# CzujnikWilgotnosciGleby_Rafal_Brauner.net
KiCad netlist of a schematic drawn in EAGLE
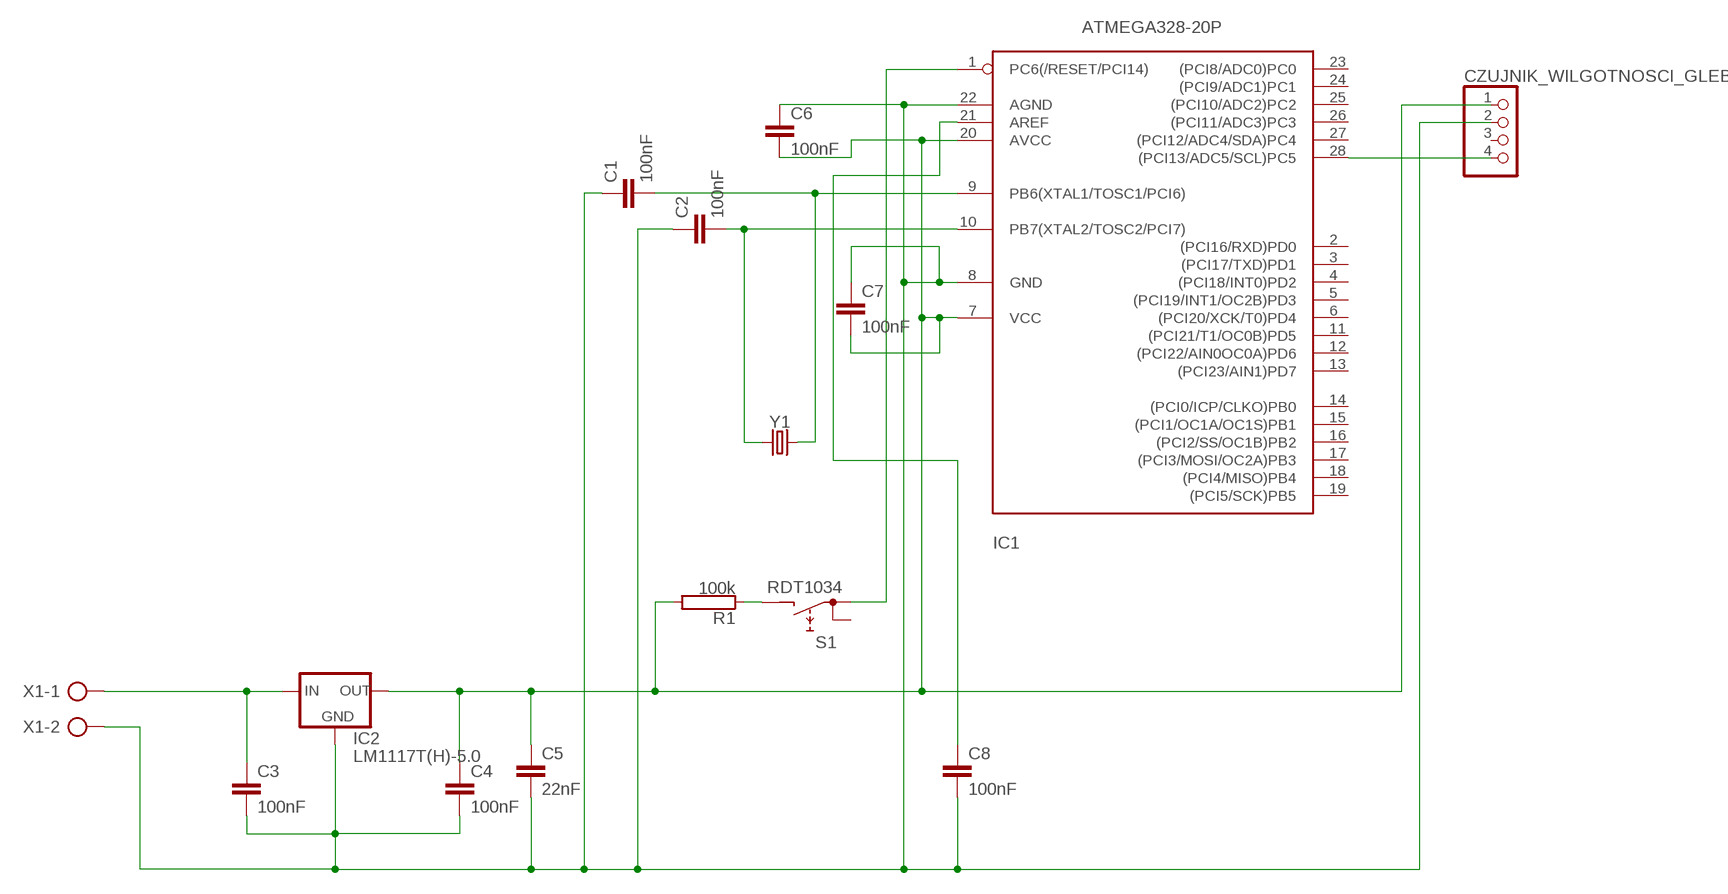
[diagram p0: schematic, sheet 1]

(export (version "E")
  (design (tool "Eeschema 10.0.6"))
  (components
    (comp (ref "C1")
      (value "100nF")
      (footprint "eagle-import:C2.5-3")
      (libsource (lib "eagle-import") (part "C2,5-3"))
    )
    (comp (ref "C2")
      (value "100nF")
      (footprint "eagle-import:C2.5-3")
      (libsource (lib "eagle-import") (part "C2,5-3"))
    )
    (comp (ref "C3")
      (value "100nF")
      (footprint "eagle-import:C2.5-3")
      (libsource (lib "eagle-import") (part "C2,5-3"))
    )
    (comp (ref "C4")
      (value "100nF")
      (footprint "eagle-import:C2.5-3")
      (libsource (lib "eagle-import") (part "C2,5-3"))
    )
    (comp (ref "C5")
      (value "22nF")
      (footprint "eagle-import:C2.5-3")
      (libsource (lib "eagle-import") (part "C2,5-3"))
    )
    (comp (ref "C6")
      (value "100nF")
      (footprint "eagle-import:C2.5-3")
      (libsource (lib "eagle-import") (part "C2,5-3"))
    )
    (comp (ref "C7")
      (value "100nF")
      (footprint "eagle-import:C2.5-3")
      (libsource (lib "eagle-import") (part "C2,5-3"))
    )
    (comp (ref "C8")
      (value "100nF")
      (footprint "eagle-import:C2.5-3")
      (libsource (lib "eagle-import") (part "C2,5-3"))
    )
    (comp (ref "CZUJNIK_WILGOTNOSCI_GLEBY")
      (value "PINHD-1X4")
      (footprint "eagle-import:1X04")
      (libsource (lib "eagle-import") (part "PINHD-1X4"))
    )
    (comp (ref "IC1")
      (value "ATMEGA328-20P")
      (footprint "eagle-import:DIL28-3")
      (libsource (lib "eagle-import") (part "ATMEGA328P-20"))
    )
    (comp (ref "IC2")
      (value "LM1117T(H)-5.0")
      (footprint "eagle-import:TO220H")
      (fields (field (name "MF") "Texas Instruments") (field (name "MPN") "LM1117T-5.0"))
      (libsource (lib "eagle-import") (part "LM1117?-T(H)5.0"))
    )
    (comp (ref "R1")
      (value "100k")
      (footprint "eagle-import:AC01")
      (libsource (lib "eagle-import") (part "RAC01"))
    )
    (comp (ref "S1")
      (value "RDT1034")
      (footprint "eagle-import:RDT1034")
      (libsource (lib "eagle-import") (part "RDT1034"))
    )
    (comp (ref "X1")
      (value "AK300/2")
      (footprint "eagle-import:AK300_2")
      (libsource (lib "eagle-import") (part "AK300/2"))
    )
    (comp (ref "Y1")
      (value "CRYSTALPTH-HC49US")
      (footprint "eagle-import:HC49US")
      (libsource (lib "eagle-import") (part "CRYSTALPTH-HC49US"))
    )
  )
  (nets
    (net (code "1") (name "Net-(IC1-(PCI13{slash}ADC5{slash}SCL)PC5)") (class "Default")
      (node (ref "CZUJNIK_WILGOTNOSCI_GLEBY") (pin "4") (pinfunction "4_4") (pintype "passive"))
      (node (ref "IC1") (pin "28") (pinfunction "(PCI13/ADC5/SCL)PC5_28") (pintype "bidirectional"))
    )
    (net (code "2") (name "Net-(IC1-AGND)") (class "Default")
      (node (ref "C1") (pin "1") (pinfunction "1_1") (pintype "passive"))
      (node (ref "C2") (pin "1") (pinfunction "1_1") (pintype "passive"))
      (node (ref "C3") (pin "2") (pinfunction "2_2") (pintype "passive"))
      (node (ref "C4") (pin "2") (pinfunction "2_2") (pintype "passive"))
      (node (ref "C5") (pin "2") (pinfunction "2_2") (pintype "passive"))
      (node (ref "C6") (pin "1") (pinfunction "1_1") (pintype "passive"))
      (node (ref "C7") (pin "1") (pinfunction "1_1") (pintype "passive"))
      (node (ref "C8") (pin "2") (pinfunction "2_2") (pintype "passive"))
      (node (ref "CZUJNIK_WILGOTNOSCI_GLEBY") (pin "2") (pinfunction "2_2") (pintype "passive"))
      (node (ref "IC1") (pin "22") (pinfunction "AGND_22") (pintype "bidirectional"))
      (node (ref "IC1") (pin "8") (pinfunction "GND_8") (pintype "bidirectional"))
      (node (ref "IC2") (pin "1") (pinfunction "GND_1") (pintype "input"))
      (node (ref "X1") (pin "2") (pinfunction "KL_2") (pintype "passive"))
    )
    (net (code "3") (name "Net-(IC1-AREF)") (class "Default")
      (node (ref "C8") (pin "1") (pinfunction "1_1") (pintype "passive"))
      (node (ref "IC1") (pin "21") (pinfunction "AREF_21") (pintype "bidirectional"))
    )
    (net (code "4") (name "Net-(IC1-AVCC)") (class "Default")
      (node (ref "C4") (pin "1") (pinfunction "1_1") (pintype "passive"))
      (node (ref "C5") (pin "1") (pinfunction "1_1") (pintype "passive"))
      (node (ref "C6") (pin "2") (pinfunction "2_2") (pintype "passive"))
      (node (ref "C7") (pin "2") (pinfunction "2_2") (pintype "passive"))
      (node (ref "CZUJNIK_WILGOTNOSCI_GLEBY") (pin "1") (pinfunction "1_1") (pintype "passive"))
      (node (ref "IC1") (pin "20") (pinfunction "AVCC_20") (pintype "bidirectional"))
      (node (ref "IC1") (pin "7") (pinfunction "VCC_7") (pintype "bidirectional"))
      (node (ref "IC2") (pin "2") (pinfunction "OUT_2") (pintype "passive"))
      (node (ref "R1") (pin "2") (pinfunction "2_2") (pintype "passive"))
    )
    (net (code "5") (name "Net-(IC1-PB6(XTAL1{slash}TOSC1{slash}PCI6))") (class "Default")
      (node (ref "C1") (pin "2") (pinfunction "2_2") (pintype "passive"))
      (node (ref "IC1") (pin "9") (pinfunction "PB6(XTAL1/TOSC1/PCI6)_9") (pintype "bidirectional"))
      (node (ref "Y1") (pin "2") (pinfunction "2_2") (pintype "passive"))
    )
    (net (code "6") (name "Net-(IC1-PB7(XTAL2{slash}TOSC2{slash}PCI7))") (class "Default")
      (node (ref "C2") (pin "2") (pinfunction "2_2") (pintype "passive"))
      (node (ref "IC1") (pin "10") (pinfunction "PB7(XTAL2/TOSC2/PCI7)_10") (pintype "bidirectional"))
      (node (ref "Y1") (pin "1") (pinfunction "1_1") (pintype "passive"))
    )
    (net (code "7") (name "Net-(IC1-PC6({slash}RESET{slash}PCI14))") (class "Default")
      (node (ref "IC1") (pin "1") (pinfunction "PC6(/RESET/PCI14)_1") (pintype "bidirectional"))
      (node (ref "S1") (pin "A1") (pinfunction "A1_A1") (pintype "passive"))
    )
    (net (code "8") (name "Net-(IC2-IN)") (class "Default")
      (node (ref "C3") (pin "1") (pinfunction "1_1") (pintype "passive"))
      (node (ref "IC2") (pin "3") (pinfunction "IN_3") (pintype "input"))
      (node (ref "X1") (pin "1") (pinfunction "KL_1") (pintype "passive"))
    )
    (net (code "9") (name "Net-(R1-Pad1)") (class "Default")
      (node (ref "R1") (pin "1") (pinfunction "1_1") (pintype "passive"))
      (node (ref "S1") (pin "B") (pinfunction "B_B") (pintype "passive"))
    )
    (net (code "10") (name "unconnected-(CZUJNIK_WILGOTNOSCI_GLEBY-Pad3)") (class "Default")
      (node (ref "CZUJNIK_WILGOTNOSCI_GLEBY") (pin "3") (pinfunction "3_3") (pintype "passive"))
    )
    (net (code "11") (name "unconnected-(IC1-(PCI0{slash}ICP{slash}CLKO)PB0-Pad14)") (class "Default")
      (node (ref "IC1") (pin "14") (pinfunction "(PCI0/ICP/CLKO)PB0_14") (pintype "bidirectional"))
    )
    (net (code "12") (name "unconnected-(IC1-(PCI1{slash}OC1A{slash}OC1S)PB1-Pad15)") (class "Default")
      (node (ref "IC1") (pin "15") (pinfunction "(PCI1/OC1A/OC1S)PB1_15") (pintype "bidirectional"))
    )
    (net (code "13") (name "unconnected-(IC1-(PCI2{slash}SS{slash}OC1B)PB2-Pad16)") (class "Default")
      (node (ref "IC1") (pin "16") (pinfunction "(PCI2/SS/OC1B)PB2_16") (pintype "bidirectional"))
    )
    (net (code "14") (name "unconnected-(IC1-(PCI3{slash}MOSI{slash}OC2A)PB3-Pad17)") (class "Default")
      (node (ref "IC1") (pin "17") (pinfunction "(PCI3/MOSI/OC2A)PB3_17") (pintype "bidirectional"))
    )
    (net (code "15") (name "unconnected-(IC1-(PCI4{slash}MISO)PB4-Pad18)") (class "Default")
      (node (ref "IC1") (pin "18") (pinfunction "(PCI4/MISO)PB4_18") (pintype "bidirectional"))
    )
    (net (code "16") (name "unconnected-(IC1-(PCI5{slash}SCK)PB5-Pad19)") (class "Default")
      (node (ref "IC1") (pin "19") (pinfunction "(PCI5/SCK)PB5_19") (pintype "bidirectional"))
    )
    (net (code "17") (name "unconnected-(IC1-(PCI8{slash}ADC0)PC0-Pad23)") (class "Default")
      (node (ref "IC1") (pin "23") (pinfunction "(PCI8/ADC0)PC0_23") (pintype "bidirectional"))
    )
    (net (code "18") (name "unconnected-(IC1-(PCI9{slash}ADC1)PC1-Pad24)") (class "Default")
      (node (ref "IC1") (pin "24") (pinfunction "(PCI9/ADC1)PC1_24") (pintype "bidirectional"))
    )
    (net (code "19") (name "unconnected-(IC1-(PCI10{slash}ADC2)PC2-Pad25)") (class "Default")
      (node (ref "IC1") (pin "25") (pinfunction "(PCI10/ADC2)PC2_25") (pintype "bidirectional"))
    )
    (net (code "20") (name "unconnected-(IC1-(PCI11{slash}ADC3)PC3-Pad26)") (class "Default")
      (node (ref "IC1") (pin "26") (pinfunction "(PCI11/ADC3)PC3_26") (pintype "bidirectional"))
    )
    (net (code "21") (name "unconnected-(IC1-(PCI12{slash}ADC4{slash}SDA)PC4-Pad27)") (class "Default")
      (node (ref "IC1") (pin "27") (pinfunction "(PCI12/ADC4/SDA)PC4_27") (pintype "bidirectional"))
    )
    (net (code "22") (name "unconnected-(IC1-(PCI16{slash}RXD)PD0-Pad2)") (class "Default")
      (node (ref "IC1") (pin "2") (pinfunction "(PCI16/RXD)PD0_2") (pintype "bidirectional"))
    )
    (net (code "23") (name "unconnected-(IC1-(PCI17{slash}TXD)PD1-Pad3)") (class "Default")
      (node (ref "IC1") (pin "3") (pinfunction "(PCI17/TXD)PD1_3") (pintype "bidirectional"))
    )
    (net (code "24") (name "unconnected-(IC1-(PCI18{slash}INT0)PD2-Pad4)") (class "Default")
      (node (ref "IC1") (pin "4") (pinfunction "(PCI18/INT0)PD2_4") (pintype "bidirectional"))
    )
    (net (code "25") (name "unconnected-(IC1-(PCI19{slash}INT1{slash}OC2B)PD3-Pad5)") (class "Default")
      (node (ref "IC1") (pin "5") (pinfunction "(PCI19/INT1/OC2B)PD3_5") (pintype "bidirectional"))
    )
    (net (code "26") (name "unconnected-(IC1-(PCI20{slash}XCK{slash}T0)PD4-Pad6)") (class "Default")
      (node (ref "IC1") (pin "6") (pinfunction "(PCI20/XCK/T0)PD4_6") (pintype "bidirectional"))
    )
    (net (code "27") (name "unconnected-(IC1-(PCI21{slash}T1{slash}OC0B)PD5-Pad11)") (class "Default")
      (node (ref "IC1") (pin "11") (pinfunction "(PCI21/T1/OC0B)PD5_11") (pintype "bidirectional"))
    )
    (net (code "28") (name "unconnected-(IC1-(PCI22{slash}AIN0OC0A)PD6-Pad12)") (class "Default")
      (node (ref "IC1") (pin "12") (pinfunction "(PCI22/AIN0OC0A)PD6_12") (pintype "bidirectional"))
    )
    (net (code "29") (name "unconnected-(IC1-(PCI23{slash}AIN1)PD7-Pad13)") (class "Default")
      (node (ref "IC1") (pin "13") (pinfunction "(PCI23/AIN1)PD7_13") (pintype "bidirectional"))
    )
    (net (code "30") (name "unconnected-(S1-PadA)") (class "Default")
      (node (ref "S1") (pin "A") (pinfunction "A_A") (pintype "passive"))
    )
  )
)
